# Schematic.net
KiCad netlist of a schematic drawn in EAGLE
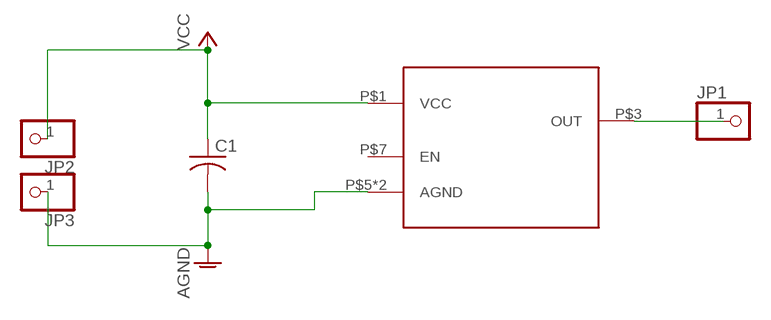
[diagram p0: schematic, sheet 1]

(export (version "E")
  (design (tool "Eeschema 10.0.6"))
  (components
    (comp (ref "C1")
      (value "C-USC0805")
      (footprint "eagle-import:C0805")
      (libsource (lib "eagle-import") (part "C-USC0805"))
    )
    (comp (ref "JP1")
      (value "PINHD-1X1")
      (footprint "eagle-import:1X01")
      (libsource (lib "eagle-import") (part "PINHD-1X1"))
    )
    (comp (ref "JP2")
      (value "PINHD-1X1")
      (footprint "eagle-import:1X01")
      (libsource (lib "eagle-import") (part "PINHD-1X1"))
    )
    (comp (ref "JP3")
      (value "PINHD-1X1")
      (footprint "eagle-import:1X01")
      (libsource (lib "eagle-import") (part "PINHD-1X1"))
    )
    (comp (ref "U$1")
      (value "MLX92213")
      (footprint "eagle-import:MLX92213")
      (libsource (lib "eagle-import") (part "MLX92213"))
    )
  )
  (nets
    (net (code "1") (name "AGND") (class "Default")
      (node (ref "C1") (pin "2") (pinfunction "2_2") (pintype "passive"))
      (node (ref "JP3") (pin "1") (pinfunction "1_1") (pintype "passive"))
      (node (ref "U$1") (pin "P$5") (pinfunction "AGND_P$5") (pintype "bidirectional"))
      (node (ref "U$1") (pin "P$8") (pinfunction "AGND_P$8") (pintype "bidirectional"))
    )
    (net (code "2") (name "Net-(U$1-OUT)") (class "Default")
      (node (ref "JP1") (pin "1") (pinfunction "1_1") (pintype "passive"))
      (node (ref "U$1") (pin "P$3") (pinfunction "OUT_P$3") (pintype "bidirectional"))
    )
    (net (code "3") (name "VCC") (class "Default")
      (node (ref "C1") (pin "1") (pinfunction "1_1") (pintype "passive"))
      (node (ref "JP2") (pin "1") (pinfunction "1_1") (pintype "passive"))
      (node (ref "U$1") (pin "P$1") (pinfunction "VCC_P$1") (pintype "bidirectional"))
    )
    (net (code "4") (name "unconnected-(U$1-EN-PadP$7)") (class "Default")
      (node (ref "U$1") (pin "P$7") (pinfunction "EN_P$7") (pintype "bidirectional"))
    )
  )
)
